# Yitran_IT900_Hutschiene_PIM7A_908_1_4_un.net
KiCad netlist of a schematic drawn in Altium Designer
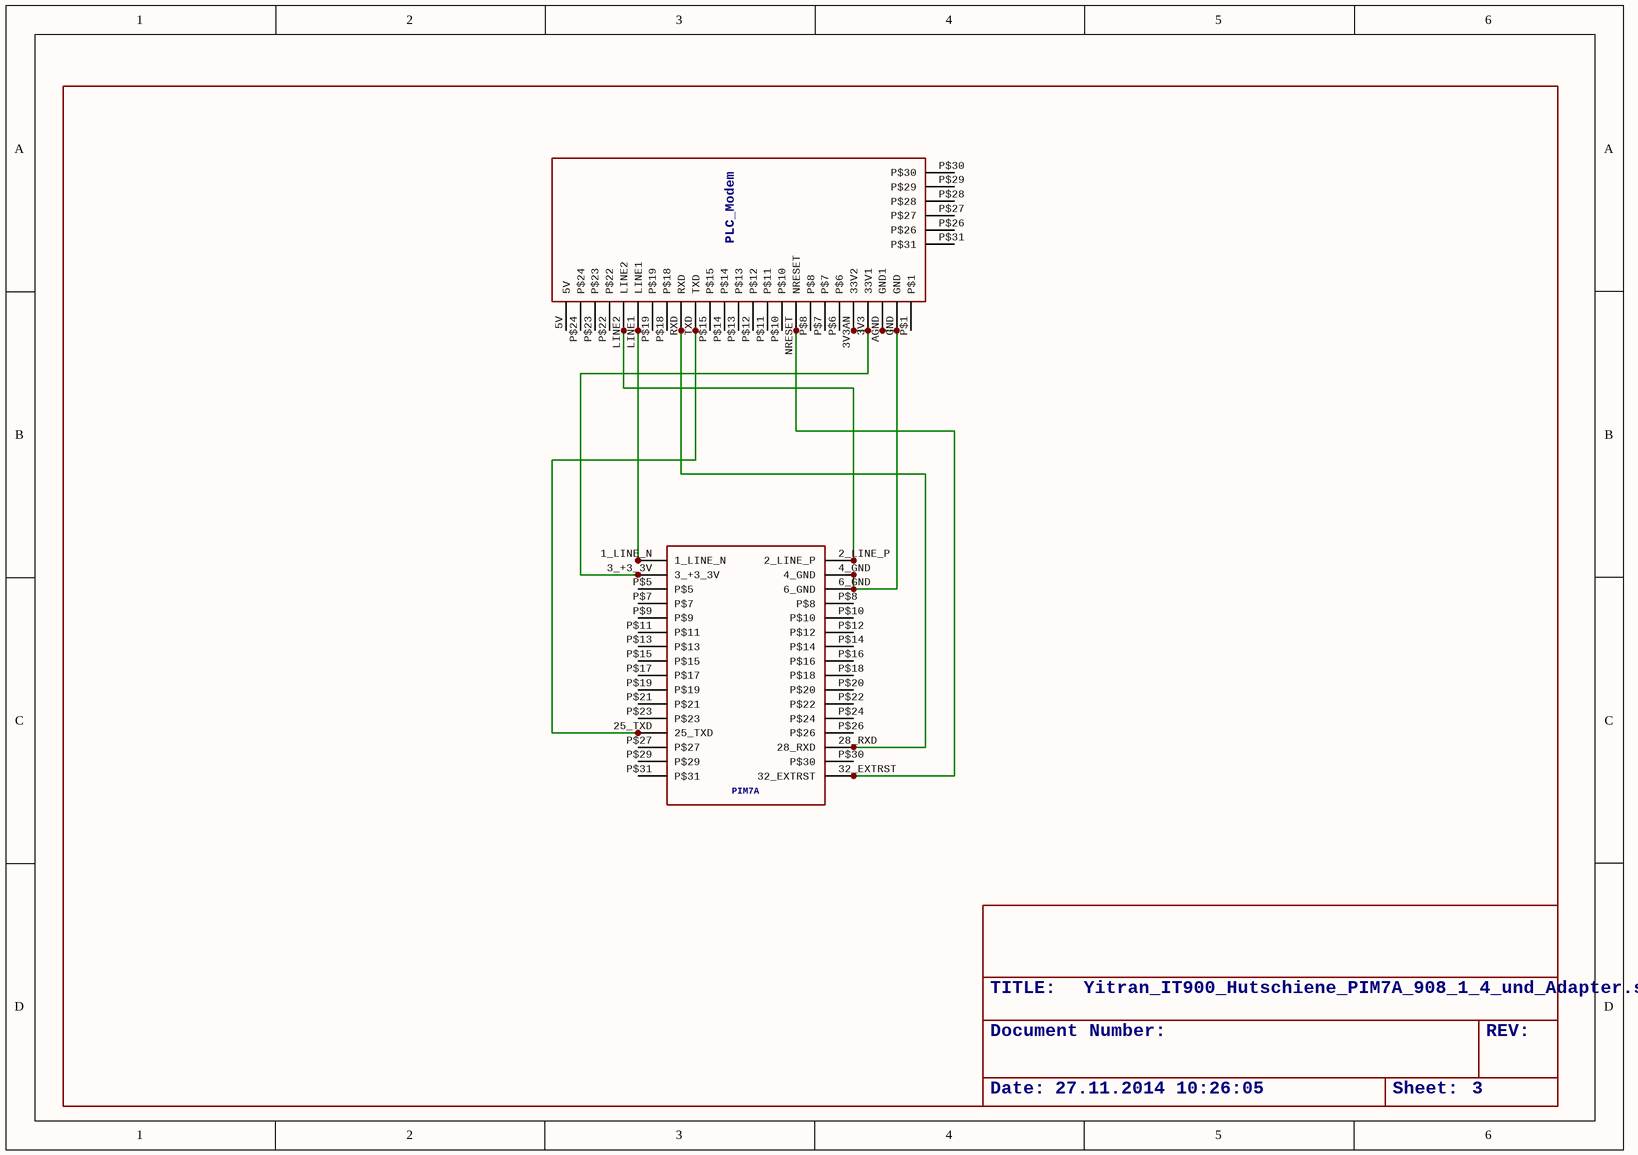
[diagram p0: Yitran_IT900_Hutschiene_PIM7A_908_1_4_und_Adapter_2.SchDoc]

(export (version "E")
  (design (tool "Eeschema 10.0.6"))
  (components
    (comp (ref "FRAME3")
      (value "DINA4_L")
      (description "<b>FRAME</b><p>\nDIN A4, landscape with extra doc field")
      (fields
        (field (name "DATE:") "Date:")
        (field (name ">LAST_DATE_TIME") "27.11.2014 10:26:05")
        (field (name "SHEET:") "Sheet:")
        (field (name ">SHEET") "3")
        (field (name "REV:") "REV:")
        (field (name "TITLE:") "TITLE:")
        (field (name "DOCUMENT NUMBER:") "Document Number:")
        (field (name ">DRAWING_NAME") "Yitran_IT900_Hutschiene_PIM7A_908_1_4_und_Adapter.sch")
      )
      (libsource (lib "frames") (part "DINA4_L"))
    )
    (comp (ref "U$7")
      (value "MODEMSTECKER_KLEINE_PINS")
      (footprint "MODEM_FUSS_KLEINE_PINS")
      (fields (field (name "PLC_MODEM") "PLC_Modem"))
      (libsource (lib "ADS1") (part "MODEMSTECKER_KLEINE_PINS"))
    )
    (comp (ref "U$8")
      (value "IT900PIM7A")
      (footprint "IT900PIM7A")
      (fields (field (name "PIM7A") "PIM7A"))
      (libsource (lib "ADS1") (part "IT900PIM7A"))
    )
  )
  (nets
    (net (code "1") (name "Net-(U$7-33V1)") (class "Default")
      (node (ref "U$7") (pin "3V3") (pinfunction "33V1_3V3") (pintype "passive"))
      (node (ref "U$7") (pin "3V3AN") (pinfunction "33V2_3V3AN") (pintype "passive"))
      (node (ref "U$8") (pin "3_+3_3V") (pinfunction "3_+3_3V_3_+3_3V") (pintype "passive"))
    )
    (net (code "2") (name "Net-(U$7-GND1)") (class "Default")
      (node (ref "U$7") (pin "AGND") (pinfunction "GND1_AGND") (pintype "passive"))
      (node (ref "U$7") (pin "GND") (pinfunction "GND_GND") (pintype "passive"))
      (node (ref "U$8") (pin "4_GND") (pinfunction "4_GND_4_GND") (pintype "passive"))
      (node (ref "U$8") (pin "6_GND") (pinfunction "6_GND_6_GND") (pintype "passive"))
    )
    (net (code "3") (name "Net-(U$7-PadLINE1)") (class "Default")
      (node (ref "U$7") (pin "LINE1") (pinfunction "LINE1_LINE1") (pintype "passive"))
      (node (ref "U$8") (pin "1_LINE_N") (pinfunction "1_LINE_N_1_LINE_N") (pintype "passive"))
    )
    (net (code "4") (name "Net-(U$7-PadLINE2)") (class "Default")
      (node (ref "U$7") (pin "LINE2") (pinfunction "LINE2_LINE2") (pintype "passive"))
      (node (ref "U$8") (pin "2_LINE_P") (pinfunction "2_LINE_P_2_LINE_P") (pintype "passive"))
    )
    (net (code "5") (name "Net-(U$7-PadNRESET)") (class "Default")
      (node (ref "U$7") (pin "NRESET") (pinfunction "NRESET_NRESET") (pintype "passive"))
      (node (ref "U$8") (pin "32_EXTRST") (pinfunction "32_EXTRST_32_EXTRST") (pintype "passive"))
    )
    (net (code "6") (name "Net-(U$7-PadRXD)") (class "Default")
      (node (ref "U$7") (pin "RXD") (pinfunction "RXD_RXD") (pintype "passive"))
      (node (ref "U$8") (pin "28_RXD") (pinfunction "28_RXD_28_RXD") (pintype "passive"))
    )
    (net (code "7") (name "Net-(U$7-PadTXD)") (class "Default")
      (node (ref "U$7") (pin "TXD") (pinfunction "TXD_TXD") (pintype "passive"))
      (node (ref "U$8") (pin "25_TXD") (pinfunction "25_TXD_25_TXD") (pintype "passive"))
    )
    (net (code "8") (name "unconnected-(U$7-Pad5V)") (class "Default")
      (node (ref "U$7") (pin "5V") (pinfunction "5V_5V") (pintype "passive"))
    )
    (net (code "9") (name "unconnected-(U$7-PadP$1)") (class "Default")
      (node (ref "U$7") (pin "P$1") (pinfunction "P$1_P$1") (pintype "passive"))
    )
    (net (code "10") (name "unconnected-(U$7-PadP$6)") (class "Default")
      (node (ref "U$7") (pin "P$6") (pinfunction "P$6_P$6") (pintype "passive"))
    )
    (net (code "11") (name "unconnected-(U$7-PadP$7)") (class "Default")
      (node (ref "U$7") (pin "P$7") (pinfunction "P$7_P$7") (pintype "passive"))
    )
    (net (code "12") (name "unconnected-(U$7-PadP$8)") (class "Default")
      (node (ref "U$7") (pin "P$8") (pinfunction "P$8_P$8") (pintype "passive"))
    )
    (net (code "13") (name "unconnected-(U$7-PadP$10)") (class "Default")
      (node (ref "U$7") (pin "P$10") (pinfunction "P$10_P$10") (pintype "passive"))
    )
    (net (code "14") (name "unconnected-(U$7-PadP$11)") (class "Default")
      (node (ref "U$7") (pin "P$11") (pinfunction "P$11_P$11") (pintype "passive"))
    )
    (net (code "15") (name "unconnected-(U$7-PadP$12)") (class "Default")
      (node (ref "U$7") (pin "P$12") (pinfunction "P$12_P$12") (pintype "passive"))
    )
    (net (code "16") (name "unconnected-(U$7-PadP$13)") (class "Default")
      (node (ref "U$7") (pin "P$13") (pinfunction "P$13_P$13") (pintype "passive"))
    )
    (net (code "17") (name "unconnected-(U$7-PadP$14)") (class "Default")
      (node (ref "U$7") (pin "P$14") (pinfunction "P$14_P$14") (pintype "passive"))
    )
    (net (code "18") (name "unconnected-(U$7-PadP$15)") (class "Default")
      (node (ref "U$7") (pin "P$15") (pinfunction "P$15_P$15") (pintype "passive"))
    )
    (net (code "19") (name "unconnected-(U$7-PadP$18)") (class "Default")
      (node (ref "U$7") (pin "P$18") (pinfunction "P$18_P$18") (pintype "passive"))
    )
    (net (code "20") (name "unconnected-(U$7-PadP$19)") (class "Default")
      (node (ref "U$7") (pin "P$19") (pinfunction "P$19_P$19") (pintype "passive"))
    )
    (net (code "21") (name "unconnected-(U$7-PadP$22)") (class "Default")
      (node (ref "U$7") (pin "P$22") (pinfunction "P$22_P$22") (pintype "passive"))
    )
    (net (code "22") (name "unconnected-(U$7-PadP$23)") (class "Default")
      (node (ref "U$7") (pin "P$23") (pinfunction "P$23_P$23") (pintype "passive"))
    )
    (net (code "23") (name "unconnected-(U$7-PadP$24)") (class "Default")
      (node (ref "U$7") (pin "P$24") (pinfunction "P$24_P$24") (pintype "passive"))
    )
    (net (code "24") (name "unconnected-(U$7-PadP$26)") (class "Default")
      (node (ref "U$7") (pin "P$26") (pinfunction "P$26_P$26") (pintype "passive"))
    )
    (net (code "25") (name "unconnected-(U$7-PadP$27)") (class "Default")
      (node (ref "U$7") (pin "P$27") (pinfunction "P$27_P$27") (pintype "passive"))
    )
    (net (code "26") (name "unconnected-(U$7-PadP$28)") (class "Default")
      (node (ref "U$7") (pin "P$28") (pinfunction "P$28_P$28") (pintype "passive"))
    )
    (net (code "27") (name "unconnected-(U$7-PadP$29)") (class "Default")
      (node (ref "U$7") (pin "P$29") (pinfunction "P$29_P$29") (pintype "passive"))
    )
    (net (code "28") (name "unconnected-(U$7-PadP$30)") (class "Default")
      (node (ref "U$7") (pin "P$30") (pinfunction "P$30_P$30") (pintype "passive"))
    )
    (net (code "29") (name "unconnected-(U$7-PadP$31)") (class "Default")
      (node (ref "U$7") (pin "P$31") (pinfunction "P$31_P$31") (pintype "passive"))
    )
    (net (code "30") (name "unconnected-(U$8-PadP$5)") (class "Default")
      (node (ref "U$8") (pin "P$5") (pinfunction "P$5_P$5") (pintype "passive"))
    )
    (net (code "31") (name "unconnected-(U$8-PadP$7)") (class "Default")
      (node (ref "U$8") (pin "P$7") (pinfunction "P$7_P$7") (pintype "passive"))
    )
    (net (code "32") (name "unconnected-(U$8-PadP$8)") (class "Default")
      (node (ref "U$8") (pin "P$8") (pinfunction "P$8_P$8") (pintype "passive"))
    )
    (net (code "33") (name "unconnected-(U$8-PadP$9)") (class "Default")
      (node (ref "U$8") (pin "P$9") (pinfunction "P$9_P$9") (pintype "passive"))
    )
    (net (code "34") (name "unconnected-(U$8-PadP$10)") (class "Default")
      (node (ref "U$8") (pin "P$10") (pinfunction "P$10_P$10") (pintype "passive"))
    )
    (net (code "35") (name "unconnected-(U$8-PadP$11)") (class "Default")
      (node (ref "U$8") (pin "P$11") (pinfunction "P$11_P$11") (pintype "passive"))
    )
    (net (code "36") (name "unconnected-(U$8-PadP$12)") (class "Default")
      (node (ref "U$8") (pin "P$12") (pinfunction "P$12_P$12") (pintype "passive"))
    )
    (net (code "37") (name "unconnected-(U$8-PadP$13)") (class "Default")
      (node (ref "U$8") (pin "P$13") (pinfunction "P$13_P$13") (pintype "passive"))
    )
    (net (code "38") (name "unconnected-(U$8-PadP$14)") (class "Default")
      (node (ref "U$8") (pin "P$14") (pinfunction "P$14_P$14") (pintype "passive"))
    )
    (net (code "39") (name "unconnected-(U$8-PadP$15)") (class "Default")
      (node (ref "U$8") (pin "P$15") (pinfunction "P$15_P$15") (pintype "passive"))
    )
    (net (code "40") (name "unconnected-(U$8-PadP$16)") (class "Default")
      (node (ref "U$8") (pin "P$16") (pinfunction "P$16_P$16") (pintype "passive"))
    )
    (net (code "41") (name "unconnected-(U$8-PadP$17)") (class "Default")
      (node (ref "U$8") (pin "P$17") (pinfunction "P$17_P$17") (pintype "passive"))
    )
    (net (code "42") (name "unconnected-(U$8-PadP$18)") (class "Default")
      (node (ref "U$8") (pin "P$18") (pinfunction "P$18_P$18") (pintype "passive"))
    )
    (net (code "43") (name "unconnected-(U$8-PadP$19)") (class "Default")
      (node (ref "U$8") (pin "P$19") (pinfunction "P$19_P$19") (pintype "passive"))
    )
    (net (code "44") (name "unconnected-(U$8-PadP$20)") (class "Default")
      (node (ref "U$8") (pin "P$20") (pinfunction "P$20_P$20") (pintype "passive"))
    )
    (net (code "45") (name "unconnected-(U$8-PadP$21)") (class "Default")
      (node (ref "U$8") (pin "P$21") (pinfunction "P$21_P$21") (pintype "passive"))
    )
    (net (code "46") (name "unconnected-(U$8-PadP$22)") (class "Default")
      (node (ref "U$8") (pin "P$22") (pinfunction "P$22_P$22") (pintype "passive"))
    )
    (net (code "47") (name "unconnected-(U$8-PadP$23)") (class "Default")
      (node (ref "U$8") (pin "P$23") (pinfunction "P$23_P$23") (pintype "passive"))
    )
    (net (code "48") (name "unconnected-(U$8-PadP$24)") (class "Default")
      (node (ref "U$8") (pin "P$24") (pinfunction "P$24_P$24") (pintype "passive"))
    )
    (net (code "49") (name "unconnected-(U$8-PadP$26)") (class "Default")
      (node (ref "U$8") (pin "P$26") (pinfunction "P$26_P$26") (pintype "passive"))
    )
    (net (code "50") (name "unconnected-(U$8-PadP$27)") (class "Default")
      (node (ref "U$8") (pin "P$27") (pinfunction "P$27_P$27") (pintype "passive"))
    )
    (net (code "51") (name "unconnected-(U$8-PadP$29)") (class "Default")
      (node (ref "U$8") (pin "P$29") (pinfunction "P$29_P$29") (pintype "passive"))
    )
    (net (code "52") (name "unconnected-(U$8-PadP$30)") (class "Default")
      (node (ref "U$8") (pin "P$30") (pinfunction "P$30_P$30") (pintype "passive"))
    )
    (net (code "53") (name "unconnected-(U$8-PadP$31)") (class "Default")
      (node (ref "U$8") (pin "P$31") (pinfunction "P$31_P$31") (pintype "passive"))
    )
  )
)
